# H_Bridge.net
KiCad netlist of a schematic drawn in Altium Designer
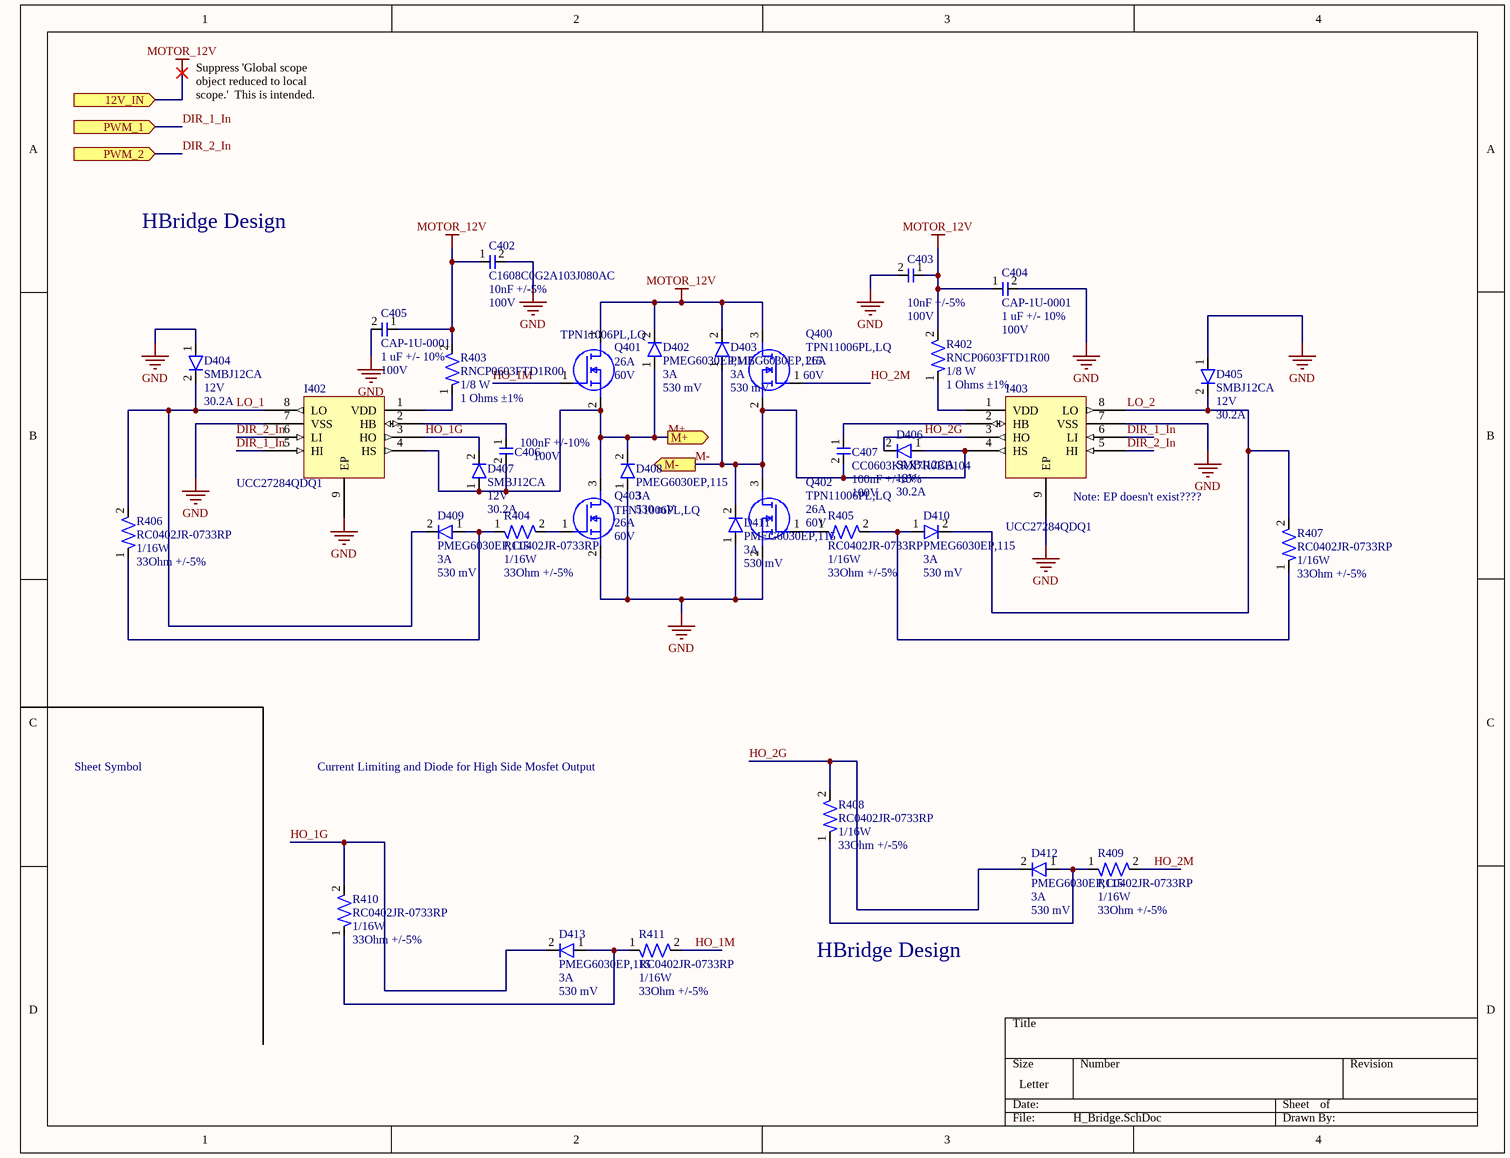
[diagram p0: H_Bridge.SchDoc]

(export (version "E")
  (design (tool "Eeschema 10.0.6"))
  (components
    (comp (ref "C402")
      (value "C1608C0G2A103J080AC")
      (footprint "CAP-0603")
      (description "CAP CER 10000PF 100V C0G 0603")
      (fields
        (field (name "MANUFACTURER") "TDK Corporation")
        (field (name "CAPACITANCE") "10nF +/-5%")
        (field (name "VOLTAGE RATING") "100V")
      )
      (libsource (lib "MasterLib") (part "CAP-10N-0002"))
    )
    (comp (ref "C403")
      (value "C1608C0G2A103J080AC")
      (footprint "CAP-0603")
      (description "CAP CER 10000PF 100V C0G 0603")
      (fields
        (field (name "MANUFACTURER") "TDK Corporation")
        (field (name "CAPACITANCE") "10nF +/-5%")
        (field (name "VOLTAGE RATING") "100V")
      )
      (libsource (lib "MasterLib") (part "CAP-10N-0002"))
    )
    (comp (ref "C404")
      (value "CAP-1U-0001")
      (footprint "CAP-1206 - duplicate")
      (description "1 µF ±10% 100V Ceramic Capacitor X7R 1206 (3216 Metric)")
      (fields (field (name "CAPACITANCE") "1 uF +/- 10%") (field (name "VOLTAGE") "100V"))
      (libsource (lib "MasterLib") (part "CAP-1U-0001"))
    )
    (comp (ref "C405")
      (value "CAP-1U-0001")
      (footprint "CAP-1206 - duplicate")
      (description "1 µF ±10% 100V Ceramic Capacitor X7R 1206 (3216 Metric)")
      (fields (field (name "CAPACITANCE") "1 uF +/- 10%") (field (name "VOLTAGE") "100V"))
      (libsource (lib "MasterLib") (part "CAP-1U-0001"))
    )
    (comp (ref "C406")
      (value "CC0603KRX7R0BB104")
      (footprint "CAP-0603")
      (description "CAP CER 0.1UF 100V X7R 0603")
      (fields
        (field (name "MANUFACTURER") "YAGEO")
        (field (name "CAPACITANCE") "100nF +/-10%")
        (field (name "VOLTAGE RATING") "100V")
      )
      (libsource (lib "MasterLib") (part "CAP-100N-0001"))
    )
    (comp (ref "C407")
      (value "CC0603KRX7R0BB104")
      (footprint "CAP-0603")
      (description "CAP CER 0.1UF 100V X7R 0603")
      (fields
        (field (name "MANUFACTURER") "YAGEO")
        (field (name "CAPACITANCE") "100nF +/-10%")
        (field (name "VOLTAGE RATING") "100V")
      )
      (libsource (lib "MasterLib") (part "CAP-100N-0001"))
    )
    (comp (ref "D402")
      (value "PMEG6030EP,115")
      (footprint "DIO-SOD128")
      (description "Diode Schottky 60 V 3A Surface Mount SOD-128/CFP5")
      (fields
        (field (name "MANUFACTURER") "Nexperia USA Inc.")
        (field (name "CURRENT RATING") "3A")
        (field (name "VF (VOLTAGE FORWARD)") "530 mV")
      )
      (libsource (lib "MasterLib") (part "DIO-0.53V-0001"))
    )
    (comp (ref "D403")
      (value "PMEG6030EP,115")
      (footprint "DIO-SOD128")
      (description "Diode Schottky 60 V 3A Surface Mount SOD-128/CFP5")
      (fields
        (field (name "MANUFACTURER") "Nexperia USA Inc.")
        (field (name "CURRENT RATING") "3A")
        (field (name "VF (VOLTAGE FORWARD)") "530 mV")
      )
      (libsource (lib "MasterLib") (part "DIO-0.53V-0001"))
    )
    (comp (ref "D404")
      (value "SMBJ12CA")
      (footprint "DO-214AA (SMBJ)")
      (description "19.9V Clamp 30.2A Ipp Tvs Diode Surface Mount DO-214AA (SMBJ)")
      (fields
        (field (name "MANUFACTURER") "Littlefuse Inc.")
        (field (name "STANDOFF VOLTAGE") "12V")
        (field (name "CURRENT RATING") "30.2A")
      )
      (libsource (lib "MasterLib") (part "DIO-19.9V-0001"))
    )
    (comp (ref "D405")
      (value "SMBJ12CA")
      (footprint "DO-214AA (SMBJ)")
      (description "19.9V Clamp 30.2A Ipp Tvs Diode Surface Mount DO-214AA (SMBJ)")
      (fields
        (field (name "MANUFACTURER") "Littlefuse Inc.")
        (field (name "STANDOFF VOLTAGE") "12V")
        (field (name "CURRENT RATING") "30.2A")
      )
      (libsource (lib "MasterLib") (part "DIO-19.9V-0001"))
    )
    (comp (ref "D406")
      (value "SMBJ12CA")
      (footprint "DO-214AA (SMBJ)")
      (description "19.9V Clamp 30.2A Ipp Tvs Diode Surface Mount DO-214AA (SMBJ)")
      (fields
        (field (name "MANUFACTURER") "Littlefuse Inc.")
        (field (name "STANDOFF VOLTAGE") "12V")
        (field (name "CURRENT RATING") "30.2A")
      )
      (libsource (lib "MasterLib") (part "DIO-19.9V-0001"))
    )
    (comp (ref "D407")
      (value "SMBJ12CA")
      (footprint "DO-214AA (SMBJ)")
      (description "19.9V Clamp 30.2A Ipp Tvs Diode Surface Mount DO-214AA (SMBJ)")
      (fields
        (field (name "MANUFACTURER") "Littlefuse Inc.")
        (field (name "STANDOFF VOLTAGE") "12V")
        (field (name "CURRENT RATING") "30.2A")
      )
      (libsource (lib "MasterLib") (part "DIO-19.9V-0001"))
    )
    (comp (ref "D408")
      (value "PMEG6030EP,115")
      (footprint "DIO-SOD128")
      (description "Diode Schottky 60 V 3A Surface Mount SOD-128/CFP5")
      (fields
        (field (name "MANUFACTURER") "Nexperia USA Inc.")
        (field (name "CURRENT RATING") "3A")
        (field (name "VF (VOLTAGE FORWARD)") "530 mV")
      )
      (libsource (lib "MasterLib") (part "DIO-0.53V-0001"))
    )
    (comp (ref "D409")
      (value "PMEG6030EP,115")
      (footprint "DIO-SOD128")
      (description "Diode Schottky 60 V 3A Surface Mount SOD-128/CFP5")
      (fields
        (field (name "MANUFACTURER") "Nexperia USA Inc.")
        (field (name "CURRENT RATING") "3A")
        (field (name "VF (VOLTAGE FORWARD)") "530 mV")
      )
      (libsource (lib "MasterLib") (part "DIO-0.53V-0001"))
    )
    (comp (ref "D410")
      (value "PMEG6030EP,115")
      (footprint "DIO-SOD128")
      (description "Diode Schottky 60 V 3A Surface Mount SOD-128/CFP5")
      (fields
        (field (name "MANUFACTURER") "Nexperia USA Inc.")
        (field (name "CURRENT RATING") "3A")
        (field (name "VF (VOLTAGE FORWARD)") "530 mV")
      )
      (libsource (lib "MasterLib") (part "DIO-0.53V-0001"))
    )
    (comp (ref "D411")
      (value "PMEG6030EP,115")
      (footprint "DIO-SOD128")
      (description "Diode Schottky 60 V 3A Surface Mount SOD-128/CFP5")
      (fields
        (field (name "MANUFACTURER") "Nexperia USA Inc.")
        (field (name "CURRENT RATING") "3A")
        (field (name "VF (VOLTAGE FORWARD)") "530 mV")
      )
      (libsource (lib "MasterLib") (part "DIO-0.53V-0001"))
    )
    (comp (ref "D412")
      (value "PMEG6030EP,115")
      (footprint "DIO-SOD128")
      (description "Diode Schottky 60 V 3A Surface Mount SOD-128/CFP5")
      (fields
        (field (name "MANUFACTURER") "Nexperia USA Inc.")
        (field (name "CURRENT RATING") "3A")
        (field (name "VF (VOLTAGE FORWARD)") "530 mV")
      )
      (libsource (lib "MasterLib") (part "DIO-0.53V-0001"))
    )
    (comp (ref "D413")
      (value "PMEG6030EP,115")
      (footprint "DIO-SOD128")
      (description "Diode Schottky 60 V 3A Surface Mount SOD-128/CFP5")
      (fields
        (field (name "MANUFACTURER") "Nexperia USA Inc.")
        (field (name "CURRENT RATING") "3A")
        (field (name "VF (VOLTAGE FORWARD)") "530 mV")
      )
      (libsource (lib "MasterLib") (part "DIO-0.53V-0001"))
    )
    (comp (ref "I402")
      (value "UCC27284QDQ1")
      (footprint "IC-BUCK-8SOIC")
      (fields (field (name "MANUFACTURER") "Texas Instruments"))
      (libsource (lib "MasterLib") (part "IC-GDRV-0001"))
    )
    (comp (ref "I403")
      (value "UCC27284QDQ1")
      (footprint "IC-BUCK-8SOIC")
      (fields (field (name "MANUFACTURER") "Texas Instruments"))
      (libsource (lib "") (part "IC-GDRV-0001_1"))
    )
    (comp (ref "Q400")
      (value "TPN11006PL,LQ")
      (footprint "NMOS-8TSON")
      (description "MOSFET N-CH 60V 200MA SOT23")
      (fields
        (field (name "MANUFACTURER") "Toshiba")
        (field (name "ID-CONTINUOUS") "26A")
        (field (name "VDS-MAX") "60V")
      )
      (libsource (lib "MasterLib") (part "NMOS-26A-0001"))
    )
    (comp (ref "Q401")
      (value "TPN11006PL,LQ")
      (footprint "NMOS-8TSON")
      (description "MOSFET N-CH 60V 200MA SOT23")
      (fields
        (field (name "MANUFACTURER") "Toshiba")
        (field (name "ID-CONTINUOUS") "26A")
        (field (name "VDS-MAX") "60V")
      )
      (libsource (lib "MasterLib") (part "NMOS-26A-0001"))
    )
    (comp (ref "Q402")
      (value "TPN11006PL,LQ")
      (footprint "NMOS-8TSON")
      (description "MOSFET N-CH 60V 200MA SOT23")
      (fields
        (field (name "MANUFACTURER") "Toshiba")
        (field (name "ID-CONTINUOUS") "26A")
        (field (name "VDS-MAX") "60V")
      )
      (libsource (lib "MasterLib") (part "NMOS-26A-0001"))
    )
    (comp (ref "Q403")
      (value "TPN11006PL,LQ")
      (footprint "NMOS-8TSON")
      (description "MOSFET N-CH 60V 200MA SOT23")
      (fields
        (field (name "MANUFACTURER") "Toshiba")
        (field (name "ID-CONTINUOUS") "26A")
        (field (name "VDS-MAX") "60V")
      )
      (libsource (lib "MasterLib") (part "NMOS-26A-0001"))
    )
    (comp (ref "R402")
      (value "RNCP0603FTD1R00")
      (footprint "RES-0603")
      (description "1 Ohms ±1% 0.125W, 1/8W Chip Resistor 0603 (1608 Metric) Anti-Sulfur Thin Film")
      (fields (field (name "POWER") "1/8 W") (field (name "RESISTANCE") "1 Ohms ±1%"))
      (libsource (lib "MasterLib") (part "RES-1-0001"))
    )
    (comp (ref "R403")
      (value "RNCP0603FTD1R00")
      (footprint "RES-0603")
      (description "1 Ohms ±1% 0.125W, 1/8W Chip Resistor 0603 (1608 Metric) Anti-Sulfur Thin Film")
      (fields (field (name "POWER") "1/8 W") (field (name "RESISTANCE") "1 Ohms ±1%"))
      (libsource (lib "MasterLib") (part "RES-1-0001"))
    )
    (comp (ref "R404")
      (value "RC0402JR-0733RP")
      (footprint "RES-0402")
      (description "RES SMD 33 OHM 5% 1/16W 0402")
      (fields
        (field (name "MANUFACTURER") "YAGEO")
        (field (name "POWER RATING") "1/16W")
        (field (name "RESISTANCE") "33Ohm +/-5%")
      )
      (libsource (lib "MasterLib") (part "RES-33-0001"))
    )
    (comp (ref "R405")
      (value "RC0402JR-0733RP")
      (footprint "RES-0402")
      (description "RES SMD 33 OHM 5% 1/16W 0402")
      (fields
        (field (name "MANUFACTURER") "YAGEO")
        (field (name "POWER RATING") "1/16W")
        (field (name "RESISTANCE") "33Ohm +/-5%")
      )
      (libsource (lib "MasterLib") (part "RES-33-0001"))
    )
    (comp (ref "R406")
      (value "RC0402JR-0733RP")
      (footprint "RES-0402")
      (description "RES SMD 33 OHM 5% 1/16W 0402")
      (fields
        (field (name "MANUFACTURER") "YAGEO")
        (field (name "POWER RATING") "1/16W")
        (field (name "RESISTANCE") "33Ohm +/-5%")
      )
      (libsource (lib "MasterLib") (part "RES-33-0001"))
    )
    (comp (ref "R407")
      (value "RC0402JR-0733RP")
      (footprint "RES-0402")
      (description "RES SMD 33 OHM 5% 1/16W 0402")
      (fields
        (field (name "MANUFACTURER") "YAGEO")
        (field (name "POWER RATING") "1/16W")
        (field (name "RESISTANCE") "33Ohm +/-5%")
      )
      (libsource (lib "MasterLib") (part "RES-33-0001"))
    )
    (comp (ref "R408")
      (value "RC0402JR-0733RP")
      (footprint "RES-0402")
      (description "RES SMD 33 OHM 5% 1/16W 0402")
      (fields
        (field (name "MANUFACTURER") "YAGEO")
        (field (name "POWER RATING") "1/16W")
        (field (name "RESISTANCE") "33Ohm +/-5%")
      )
      (libsource (lib "MasterLib") (part "RES-33-0001"))
    )
    (comp (ref "R409")
      (value "RC0402JR-0733RP")
      (footprint "RES-0402")
      (description "RES SMD 33 OHM 5% 1/16W 0402")
      (fields
        (field (name "MANUFACTURER") "YAGEO")
        (field (name "POWER RATING") "1/16W")
        (field (name "RESISTANCE") "33Ohm +/-5%")
      )
      (libsource (lib "MasterLib") (part "RES-33-0001"))
    )
    (comp (ref "R410")
      (value "RC0402JR-0733RP")
      (footprint "RES-0402")
      (description "RES SMD 33 OHM 5% 1/16W 0402")
      (fields
        (field (name "MANUFACTURER") "YAGEO")
        (field (name "POWER RATING") "1/16W")
        (field (name "RESISTANCE") "33Ohm +/-5%")
      )
      (libsource (lib "MasterLib") (part "RES-33-0001"))
    )
    (comp (ref "R411")
      (value "RC0402JR-0733RP")
      (footprint "RES-0402")
      (description "RES SMD 33 OHM 5% 1/16W 0402")
      (fields
        (field (name "MANUFACTURER") "YAGEO")
        (field (name "POWER RATING") "1/16W")
        (field (name "RESISTANCE") "33Ohm +/-5%")
      )
      (libsource (lib "MasterLib") (part "RES-33-0001"))
    )
  )
  (nets
    (net (code "1") (name "/DIR_1_In") (class "Default")
      (node (ref "I402") (pin "5") (pinfunction "HI_5") (pintype "input"))
      (node (ref "I403") (pin "6") (pinfunction "LI_6") (pintype "input"))
    )
    (net (code "2") (name "/DIR_2_In") (class "Default")
      (node (ref "I402") (pin "6") (pinfunction "LI_6") (pintype "input"))
      (node (ref "I403") (pin "5") (pinfunction "HI_5") (pintype "input"))
    )
    (net (code "3") (name "/HO_1G") (class "Default")
      (node (ref "D407") (pin "2") (pintype "passive"))
      (node (ref "D413") (pin "2") (pintype "passive"))
      (node (ref "I402") (pin "3") (pinfunction "HO_3") (pintype "output"))
      (node (ref "R410") (pin "2") (pinfunction "2_2") (pintype "passive"))
    )
    (net (code "4") (name "/HO_1M") (class "Default")
      (node (ref "Q401") (pin "1") (pinfunction "G_1") (pintype "passive"))
      (node (ref "R411") (pin "2") (pinfunction "2_2") (pintype "passive"))
    )
    (net (code "5") (name "/HO_2G") (class "Default")
      (node (ref "D406") (pin "2") (pintype "passive"))
      (node (ref "D412") (pin "2") (pintype "passive"))
      (node (ref "I403") (pin "3") (pinfunction "HO_3") (pintype "output"))
      (node (ref "R408") (pin "2") (pinfunction "2_2") (pintype "passive"))
    )
    (net (code "6") (name "/HO_2M") (class "Default")
      (node (ref "Q400") (pin "1") (pinfunction "G_1") (pintype "passive"))
      (node (ref "R409") (pin "2") (pinfunction "2_2") (pintype "passive"))
    )
    (net (code "7") (name "/LO_1") (class "Default")
      (node (ref "D404") (pin "2") (pintype "passive"))
      (node (ref "D409") (pin "2") (pintype "passive"))
      (node (ref "I402") (pin "8") (pinfunction "LO_8") (pintype "output"))
      (node (ref "R406") (pin "2") (pinfunction "2_2") (pintype "passive"))
    )
    (net (code "8") (name "/LO_2") (class "Default")
      (node (ref "D405") (pin "2") (pintype "passive"))
      (node (ref "D410") (pin "2") (pintype "passive"))
      (node (ref "I403") (pin "8") (pinfunction "LO_8") (pintype "output"))
      (node (ref "R407") (pin "2") (pinfunction "2_2") (pintype "passive"))
    )
    (net (code "9") (name "/M+") (class "Default")
      (node (ref "C406") (pin "2") (pinfunction "2_2") (pintype "passive"))
      (node (ref "D402") (pin "1") (pintype "passive"))
      (node (ref "D407") (pin "1") (pintype "passive"))
      (node (ref "D408") (pin "2") (pintype "passive"))
      (node (ref "I402") (pin "4") (pinfunction "HS_4") (pintype "output"))
      (node (ref "Q401") (pin "2") (pinfunction "S_2") (pintype "passive"))
      (node (ref "Q403") (pin "3") (pinfunction "D_3") (pintype "passive"))
    )
    (net (code "10") (name "/M-") (class "Default")
      (node (ref "C407") (pin "2") (pinfunction "2_2") (pintype "passive"))
      (node (ref "D403") (pin "1") (pintype "passive"))
      (node (ref "D406") (pin "1") (pintype "passive"))
      (node (ref "D411") (pin "2") (pintype "passive"))
      (node (ref "I403") (pin "4") (pinfunction "HS_4") (pintype "output"))
      (node (ref "Q400") (pin "2") (pinfunction "S_2") (pintype "passive"))
      (node (ref "Q402") (pin "3") (pinfunction "D_3") (pintype "passive"))
    )
    (net (code "11") (name "GND") (class "Default")
      (node (ref "C402") (pin "2") (pinfunction "2_2") (pintype "passive"))
      (node (ref "C403") (pin "2") (pinfunction "2_2") (pintype "passive"))
      (node (ref "C404") (pin "2") (pinfunction "2_2") (pintype "passive"))
      (node (ref "C405") (pin "2") (pinfunction "2_2") (pintype "passive"))
      (node (ref "D404") (pin "1") (pintype "passive"))
      (node (ref "D405") (pin "1") (pintype "passive"))
      (node (ref "D408") (pin "1") (pintype "passive"))
      (node (ref "D411") (pin "1") (pintype "passive"))
      (node (ref "I402") (pin "7") (pinfunction "VSS_7") (pintype "power_in"))
      (node (ref "I402") (pin "9") (pinfunction "EP_9") (pintype "power_in"))
      (node (ref "I403") (pin "7") (pinfunction "VSS_7") (pintype "power_in"))
      (node (ref "I403") (pin "9") (pinfunction "EP_9") (pintype "power_in"))
      (node (ref "Q402") (pin "2") (pinfunction "S_2") (pintype "passive"))
      (node (ref "Q403") (pin "2") (pinfunction "S_2") (pintype "passive"))
    )
    (net (code "12") (name "MOTOR_12V") (class "Default")
      (node (ref "C402") (pin "1") (pinfunction "1_1") (pintype "passive"))
      (node (ref "C403") (pin "1") (pinfunction "1_1") (pintype "passive"))
      (node (ref "C404") (pin "1") (pinfunction "1_1") (pintype "passive"))
      (node (ref "C405") (pin "1") (pinfunction "1_1") (pintype "passive"))
      (node (ref "D402") (pin "2") (pintype "passive"))
      (node (ref "D403") (pin "2") (pintype "passive"))
      (node (ref "Q400") (pin "3") (pinfunction "D_3") (pintype "passive"))
      (node (ref "Q401") (pin "3") (pinfunction "D_3") (pintype "passive"))
      (node (ref "R402") (pin "2") (pinfunction "2_2") (pintype "passive"))
      (node (ref "R403") (pin "2") (pinfunction "2_2") (pintype "passive"))
    )
    (net (code "13") (name "Net-(D409-Pad1)") (class "Default")
      (node (ref "D409") (pin "1") (pintype "passive"))
      (node (ref "R404") (pin "1") (pinfunction "1_1") (pintype "passive"))
      (node (ref "R406") (pin "1") (pinfunction "1_1") (pintype "passive"))
    )
    (net (code "14") (name "Net-(D410-Pad1)") (class "Default")
      (node (ref "D410") (pin "1") (pintype "passive"))
      (node (ref "R405") (pin "2") (pinfunction "2_2") (pintype "passive"))
      (node (ref "R407") (pin "1") (pinfunction "1_1") (pintype "passive"))
    )
    (net (code "15") (name "Net-(D412-Pad1)") (class "Default")
      (node (ref "D412") (pin "1") (pintype "passive"))
      (node (ref "R408") (pin "1") (pinfunction "1_1") (pintype "passive"))
      (node (ref "R409") (pin "1") (pinfunction "1_1") (pintype "passive"))
    )
    (net (code "16") (name "Net-(D413-Pad1)") (class "Default")
      (node (ref "D413") (pin "1") (pintype "passive"))
      (node (ref "R410") (pin "1") (pinfunction "1_1") (pintype "passive"))
      (node (ref "R411") (pin "1") (pinfunction "1_1") (pintype "passive"))
    )
    (net (code "17") (name "Net-(I402-HB)") (class "Default")
      (node (ref "C406") (pin "1") (pinfunction "1_1") (pintype "passive"))
      (node (ref "I402") (pin "2") (pinfunction "HB_2") (pintype "bidirectional"))
    )
    (net (code "18") (name "Net-(I402-VDD)") (class "Default")
      (node (ref "I402") (pin "1") (pinfunction "VDD_1") (pintype "power_in"))
      (node (ref "R403") (pin "1") (pinfunction "1_1") (pintype "passive"))
    )
    (net (code "19") (name "Net-(I403-HB)") (class "Default")
      (node (ref "C407") (pin "1") (pinfunction "1_1") (pintype "passive"))
      (node (ref "I403") (pin "2") (pinfunction "HB_2") (pintype "bidirectional"))
    )
    (net (code "20") (name "Net-(I403-VDD)") (class "Default")
      (node (ref "I403") (pin "1") (pinfunction "VDD_1") (pintype "power_in"))
      (node (ref "R402") (pin "1") (pinfunction "1_1") (pintype "passive"))
    )
    (net (code "21") (name "Net-(Q402-G)") (class "Default")
      (node (ref "Q402") (pin "1") (pinfunction "G_1") (pintype "passive"))
      (node (ref "R405") (pin "1") (pinfunction "1_1") (pintype "passive"))
    )
    (net (code "22") (name "Net-(Q403-G)") (class "Default")
      (node (ref "Q403") (pin "1") (pinfunction "G_1") (pintype "passive"))
      (node (ref "R404") (pin "2") (pinfunction "2_2") (pintype "passive"))
    )
  )
)
